# source_eagle.net
KiCad netlist of a schematic drawn in EAGLE
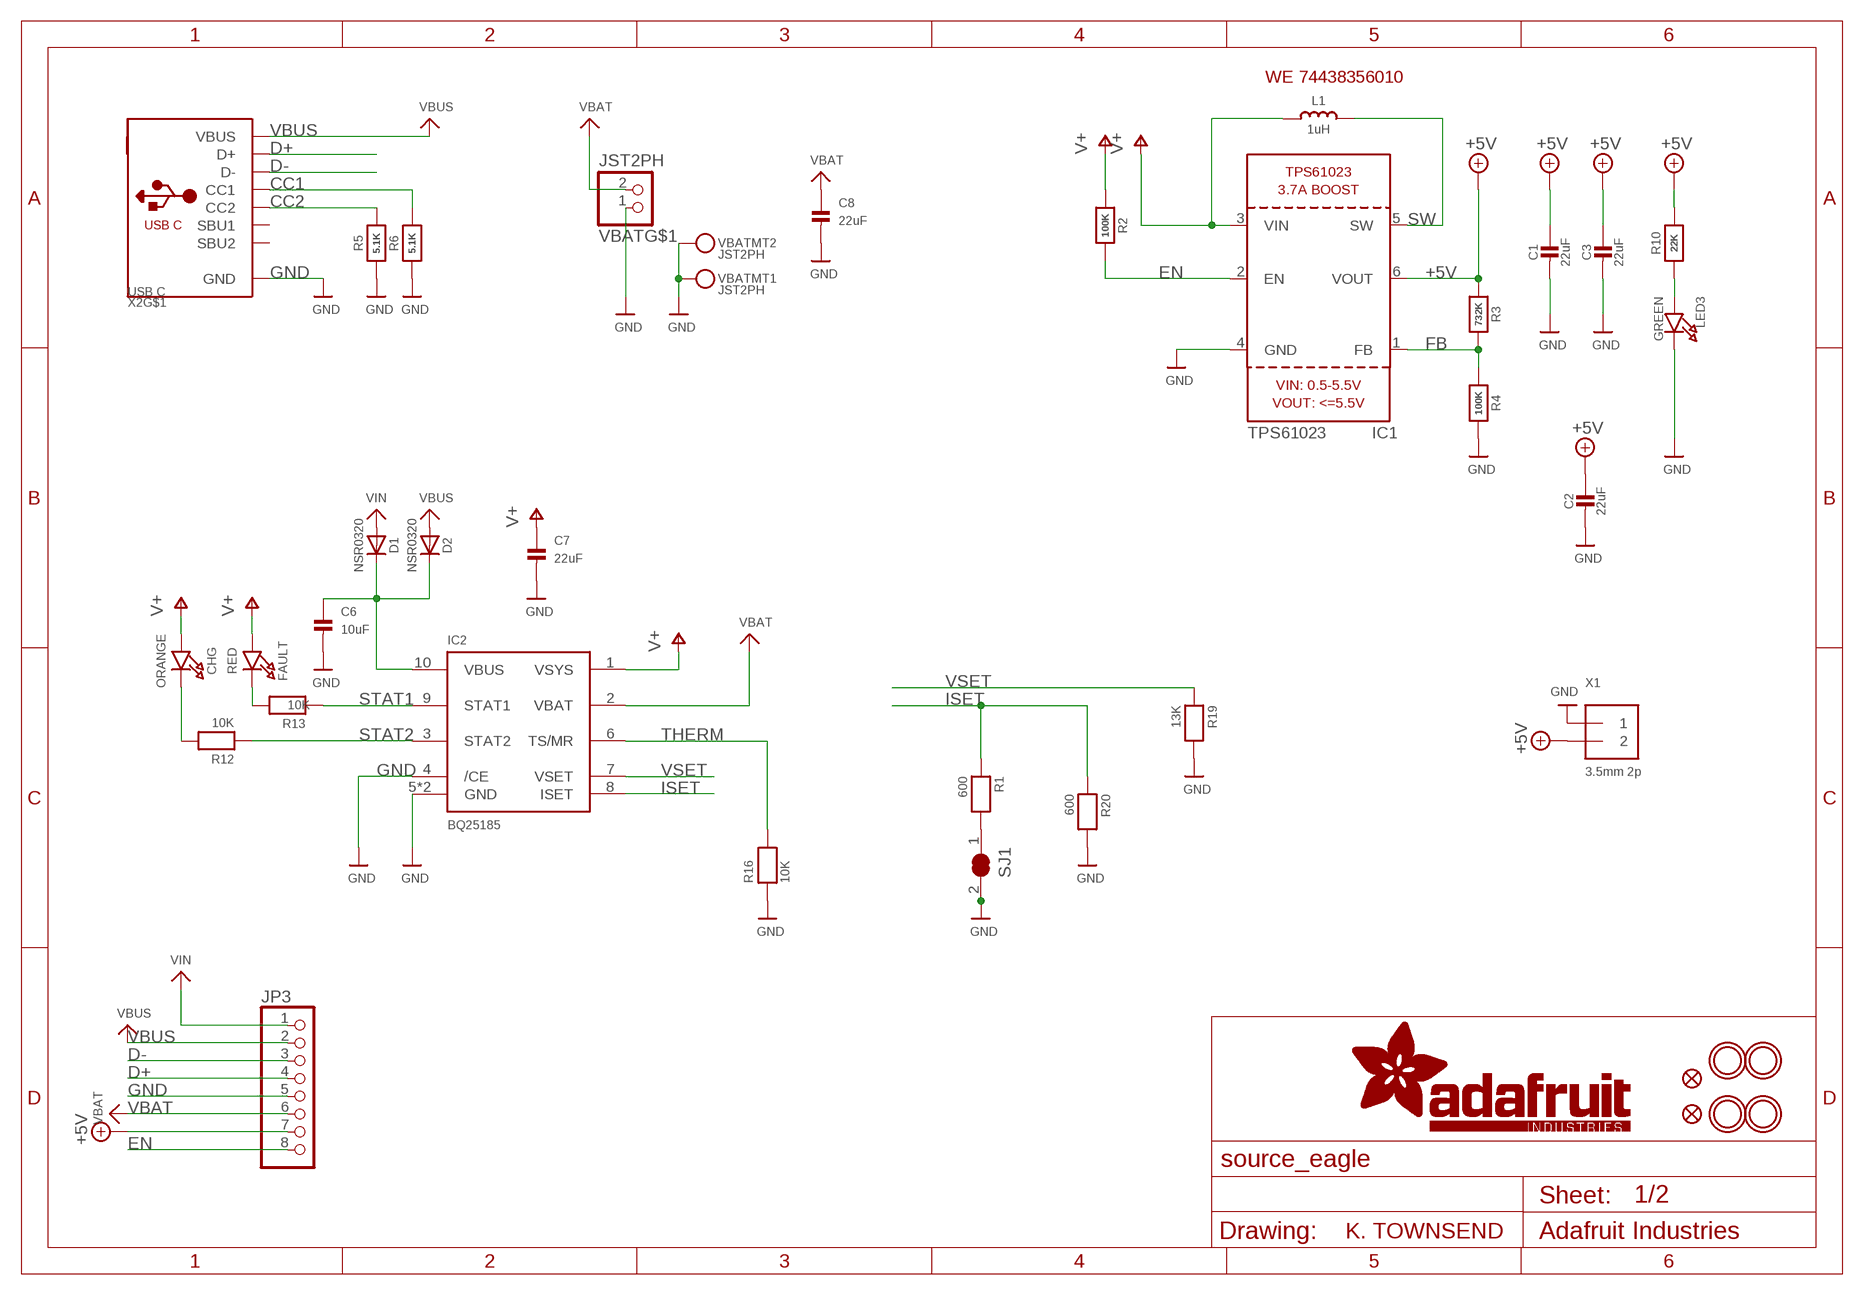
[diagram p0: schematic, sheet 1]
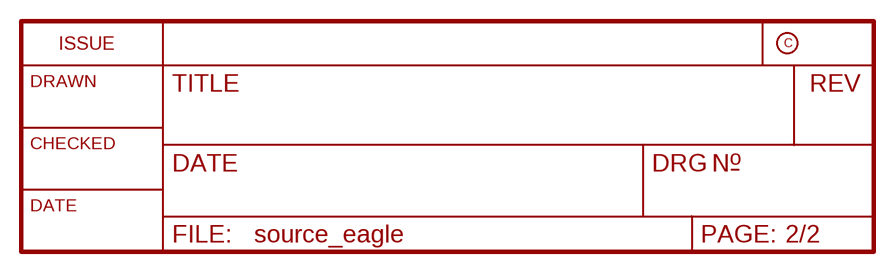
[diagram p1: schematic, sheet 2]

(export (version "E")
  (design (tool "Eeschema 10.0.6"))
  (components
    (comp (ref "C1")
      (value "22uF")
      (footprint "eagle-import:0805-NO")
      (libsource (lib "eagle-import") (part "CAP_CERAMIC0805-NOOUTLINE"))
    )
    (comp (ref "C2")
      (value "22uF")
      (footprint "eagle-import:0805-NO")
      (libsource (lib "eagle-import") (part "CAP_CERAMIC0805-NOOUTLINE"))
    )
    (comp (ref "C3")
      (value "22uF")
      (footprint "eagle-import:0805-NO")
      (libsource (lib "eagle-import") (part "CAP_CERAMIC0805-NOOUTLINE"))
    )
    (comp (ref "C6")
      (value "10uF")
      (footprint "eagle-import:0805-NO")
      (libsource (lib "eagle-import") (part "CAP_CERAMIC0805-NOOUTLINE"))
    )
    (comp (ref "C7")
      (value "22uF")
      (footprint "eagle-import:0805-NO")
      (libsource (lib "eagle-import") (part "CAP_CERAMIC0805-NOOUTLINE"))
    )
    (comp (ref "C8")
      (value "22uF")
      (footprint "eagle-import:0805-NO")
      (libsource (lib "eagle-import") (part "CAP_CERAMIC0805-NOOUTLINE"))
    )
    (comp (ref "CHG")
      (value "ORANGE")
      (footprint "eagle-import:CHIPLED_0603_NOOUTLINE")
      (libsource (lib "eagle-import") (part "LED0603_NOOUTLINE"))
    )
    (comp (ref "D1")
      (value "NSR0320")
      (footprint "eagle-import:SOD-323_MINI")
      (libsource (lib "eagle-import") (part "DIODE_SOD323MINI"))
    )
    (comp (ref "D2")
      (value "NSR0320")
      (footprint "eagle-import:SOD-323_MINI")
      (libsource (lib "eagle-import") (part "DIODE_SOD323MINI"))
    )
    (comp (ref "FAULT")
      (value "RED")
      (footprint "eagle-import:CHIPLED_0603_NOOUTLINE")
      (libsource (lib "eagle-import") (part "LED0603_NOOUTLINE"))
    )
    (comp (ref "FID1")
      (value "FIDUCIAL_0.5MM")
      (footprint "eagle-import:FIDUCIAL_0.5MM")
      (libsource (lib "eagle-import") (part "FIDUCIAL_0.5MM"))
    )
    (comp (ref "FID2")
      (value "FIDUCIAL_0.5MM")
      (footprint "eagle-import:FIDUCIAL_0.5MM")
      (libsource (lib "eagle-import") (part "FIDUCIAL_0.5MM"))
    )
    (comp (ref "IC1")
      (value "TPS61023")
      (footprint "eagle-import:SOT563")
      (libsource (lib "eagle-import") (part "TPS61023"))
    )
    (comp (ref "IC2")
      (value "BQ25185")
      (footprint "eagle-import:WSON10")
      (libsource (lib "eagle-import") (part "BQ25185"))
    )
    (comp (ref "JP3")
      (value "HEADER-1X870MIL")
      (footprint "eagle-import:1X08_ROUND_70")
      (libsource (lib "eagle-import") (part "HEADER-1X870MIL"))
    )
    (comp (ref "L1")
      (value "1uH")
      (footprint "eagle-import:INDUCTOR_5045_SMALLTABS")
      (libsource (lib "eagle-import") (part "INDUCTOR_5045_SMALLTABS"))
    )
    (comp (ref "LED3")
      (value "GREEN")
      (footprint "eagle-import:CHIPLED_0603_NOOUTLINE")
      (libsource (lib "eagle-import") (part "LED0603_NOOUTLINE"))
    )
    (comp (ref "R1")
      (value "600")
      (footprint "eagle-import:_0402NO")
      (libsource (lib "eagle-import") (part "RESISTOR_0402NO"))
    )
    (comp (ref "R2")
      (value "100K")
      (footprint "eagle-import:_0402NO")
      (libsource (lib "eagle-import") (part "RESISTOR_0402NO"))
    )
    (comp (ref "R3")
      (value "732K")
      (footprint "eagle-import:_0402NO")
      (libsource (lib "eagle-import") (part "RESISTOR_0402NO"))
    )
    (comp (ref "R4")
      (value "100K")
      (footprint "eagle-import:_0402NO")
      (libsource (lib "eagle-import") (part "RESISTOR_0402NO"))
    )
    (comp (ref "R5")
      (value "5.1K")
      (footprint "eagle-import:_0402NO")
      (libsource (lib "eagle-import") (part "RESISTOR_0402NO"))
    )
    (comp (ref "R6")
      (value "5.1K")
      (footprint "eagle-import:_0402NO")
      (libsource (lib "eagle-import") (part "RESISTOR_0402NO"))
    )
    (comp (ref "R10")
      (value "22K")
      (footprint "eagle-import:_0402NO")
      (libsource (lib "eagle-import") (part "RESISTOR_0402NO"))
    )
    (comp (ref "R12")
      (value "10K")
      (footprint "eagle-import:_0402NO")
      (libsource (lib "eagle-import") (part "RESISTOR_0402NO"))
    )
    (comp (ref "R13")
      (value "10K")
      (footprint "eagle-import:_0402NO")
      (libsource (lib "eagle-import") (part "RESISTOR_0402NO"))
    )
    (comp (ref "R16")
      (value "10K")
      (footprint "eagle-import:_0402NO")
      (libsource (lib "eagle-import") (part "RESISTOR_0402NO"))
    )
    (comp (ref "R19")
      (value "13K")
      (footprint "eagle-import:_0402NO")
      (libsource (lib "eagle-import") (part "RESISTOR_0402NO"))
    )
    (comp (ref "R20")
      (value "600")
      (footprint "eagle-import:_0402NO")
      (libsource (lib "eagle-import") (part "RESISTOR_0402NO"))
    )
    (comp (ref "SJ1")
      (value "SOLDERJUMPER_CLOSED")
      (footprint "eagle-import:SOLDERJUMPER_CLOSEDWIRE")
      (libsource (lib "eagle-import") (part "SOLDERJUMPER_CLOSED"))
    )
    (comp (ref "U$9")
      (value "MOUNTINGHOLE2.5")
      (footprint "eagle-import:MOUNTINGHOLE_2.5_PLATED")
      (libsource (lib "eagle-import") (part "MOUNTINGHOLE2.5"))
    )
    (comp (ref "U$10")
      (value "MOUNTINGHOLE2.5")
      (footprint "eagle-import:MOUNTINGHOLE_2.5_PLATED")
      (libsource (lib "eagle-import") (part "MOUNTINGHOLE2.5"))
    )
    (comp (ref "U$11")
      (value "MOUNTINGHOLE2.5")
      (footprint "eagle-import:MOUNTINGHOLE_2.5_PLATED")
      (libsource (lib "eagle-import") (part "MOUNTINGHOLE2.5"))
    )
    (comp (ref "U$12")
      (value "MOUNTINGHOLE2.5")
      (footprint "eagle-import:MOUNTINGHOLE_2.5_PLATED")
      (libsource (lib "eagle-import") (part "MOUNTINGHOLE2.5"))
    )
    (comp (ref "VBAT")
      (value "JST2PH")
      (footprint "eagle-import:JSTPH2_BATT")
      (libsource (lib "eagle-import") (part "CON_JST_PH_2PIN_MT_BATT"))
    )
    (comp (ref "X1")
      (value "3.5mm 2p")
      (footprint "eagle-import:TERMBLOCK_1X2-3.5MM")
      (libsource (lib "eagle-import") (part "TERMBLOCK_1X2_3.5MM"))
    )
    (comp (ref "X2")
      (value "USB C")
      (footprint "eagle-import:USB_C_CUSB31-CFM2AX-01-X")
      (libsource (lib "eagle-import") (part "USB_C"))
    )
  )
  (nets
    (net (code "1") (name "+5V") (class "Default")
      (node (ref "C1") (pin "1") (pinfunction "1_1") (pintype "passive"))
      (node (ref "C2") (pin "1") (pinfunction "1_1") (pintype "passive"))
      (node (ref "C3") (pin "1") (pinfunction "1_1") (pintype "passive"))
      (node (ref "IC1") (pin "6") (pinfunction "VOUT_6") (pintype "power_in"))
      (node (ref "JP3") (pin "7") (pinfunction "7_7") (pintype "passive"))
      (node (ref "R10") (pin "2") (pinfunction "2_2") (pintype "passive"))
      (node (ref "R3") (pin "1") (pinfunction "1_1") (pintype "passive"))
      (node (ref "X1") (pin "2") (pinfunction "2_2") (pintype "passive"))
    )
    (net (code "2") (name "CC1") (class "Default")
      (node (ref "R6") (pin "2") (pinfunction "2_2") (pintype "passive"))
      (node (ref "X2") (pin "A5") (pinfunction "CC1_A5") (pintype "bidirectional"))
    )
    (net (code "3") (name "CC2") (class "Default")
      (node (ref "R5") (pin "2") (pinfunction "2_2") (pintype "passive"))
      (node (ref "X2") (pin "B5") (pinfunction "CC2_B5") (pintype "bidirectional"))
    )
    (net (code "4") (name "D+") (class "Default")
      (node (ref "JP3") (pin "4") (pinfunction "4_4") (pintype "passive"))
      (node (ref "X2") (pin "A6") (pinfunction "D+_A6") (pintype "bidirectional"))
      (node (ref "X2") (pin "B6") (pinfunction "D+_B6") (pintype "bidirectional"))
    )
    (net (code "5") (name "D-") (class "Default")
      (node (ref "JP3") (pin "3") (pinfunction "3_3") (pintype "passive"))
      (node (ref "X2") (pin "A7") (pinfunction "D-_A7") (pintype "bidirectional"))
      (node (ref "X2") (pin "B7") (pinfunction "D-_B7") (pintype "bidirectional"))
    )
    (net (code "6") (name "EN") (class "Default")
      (node (ref "IC1") (pin "2") (pinfunction "EN_2") (pintype "input"))
      (node (ref "JP3") (pin "8") (pinfunction "8_8") (pintype "passive"))
      (node (ref "R2") (pin "2") (pinfunction "2_2") (pintype "passive"))
    )
    (net (code "7") (name "FB") (class "Default")
      (node (ref "IC1") (pin "1") (pinfunction "FB_1") (pintype "input"))
      (node (ref "R3") (pin "2") (pinfunction "2_2") (pintype "passive"))
      (node (ref "R4") (pin "1") (pinfunction "1_1") (pintype "passive"))
    )
    (net (code "8") (name "GND") (class "Default")
      (node (ref "C1") (pin "2") (pinfunction "2_2") (pintype "passive"))
      (node (ref "C2") (pin "2") (pinfunction "2_2") (pintype "passive"))
      (node (ref "C3") (pin "2") (pinfunction "2_2") (pintype "passive"))
      (node (ref "C6") (pin "2") (pinfunction "2_2") (pintype "passive"))
      (node (ref "C7") (pin "2") (pinfunction "2_2") (pintype "passive"))
      (node (ref "C8") (pin "2") (pinfunction "2_2") (pintype "passive"))
      (node (ref "IC1") (pin "4") (pinfunction "GND_4") (pintype "power_in"))
      (node (ref "IC2") (pin "4") (pinfunction "/CE_4") (pintype "input"))
      (node (ref "IC2") (pin "5") (pinfunction "GND_5") (pintype "bidirectional"))
      (node (ref "IC2") (pin "PAD") (pinfunction "GND_PAD") (pintype "bidirectional"))
      (node (ref "JP3") (pin "5") (pinfunction "5_5") (pintype "passive"))
      (node (ref "LED3") (pin "C") (pinfunction "C_C") (pintype "passive"))
      (node (ref "R16") (pin "1") (pinfunction "1_1") (pintype "passive"))
      (node (ref "R19") (pin "2") (pinfunction "2_2") (pintype "passive"))
      (node (ref "R20") (pin "2") (pinfunction "2_2") (pintype "passive"))
      (node (ref "R4") (pin "2") (pinfunction "2_2") (pintype "passive"))
      (node (ref "R5") (pin "1") (pinfunction "1_1") (pintype "passive"))
      (node (ref "R6") (pin "1") (pinfunction "1_1") (pintype "passive"))
      (node (ref "SJ1") (pin "2") (pinfunction "2_2") (pintype "passive"))
      (node (ref "VBAT") (pin "1") (pinfunction "1_1") (pintype "passive"))
      (node (ref "VBAT") (pin "NC1") (pinfunction "P$1_NC1") (pintype "bidirectional"))
      (node (ref "VBAT") (pin "NC2") (pinfunction "P$1_NC2") (pintype "bidirectional"))
      (node (ref "X1") (pin "1") (pinfunction "1_1") (pintype "passive"))
      (node (ref "X2") (pin "A1B12") (pinfunction "GND_A1B12") (pintype "power_in"))
      (node (ref "X2") (pin "B1A12") (pinfunction "GND_B1A12") (pintype "power_in"))
    )
    (net (code "9") (name "ISET") (class "Default")
      (node (ref "IC2") (pin "8") (pinfunction "ISET_8") (pintype "bidirectional"))
      (node (ref "R1") (pin "1") (pinfunction "1_1") (pintype "passive"))
      (node (ref "R20") (pin "1") (pinfunction "1_1") (pintype "passive"))
    )
    (net (code "10") (name "Net-(CHG-PadC)") (class "Default")
      (node (ref "CHG") (pin "C") (pinfunction "C_C") (pintype "passive"))
      (node (ref "R12") (pin "2") (pinfunction "2_2") (pintype "passive"))
    )
    (net (code "11") (name "Net-(FAULT-PadC)") (class "Default")
      (node (ref "FAULT") (pin "C") (pinfunction "C_C") (pintype "passive"))
      (node (ref "R13") (pin "2") (pinfunction "2_2") (pintype "passive"))
    )
    (net (code "12") (name "Net-(IC2-VBUS)") (class "Default")
      (node (ref "C6") (pin "1") (pinfunction "1_1") (pintype "passive"))
      (node (ref "D1") (pin "C") (pinfunction "C_C") (pintype "passive"))
      (node (ref "D2") (pin "C") (pinfunction "C_C") (pintype "passive"))
      (node (ref "IC2") (pin "10") (pinfunction "VBUS_10") (pintype "power_in"))
    )
    (net (code "13") (name "Net-(LED3-PadA)") (class "Default")
      (node (ref "LED3") (pin "A") (pinfunction "A_A") (pintype "passive"))
      (node (ref "R10") (pin "1") (pinfunction "1_1") (pintype "passive"))
    )
    (net (code "14") (name "Net-(R1-Pad2)") (class "Default")
      (node (ref "R1") (pin "2") (pinfunction "2_2") (pintype "passive"))
      (node (ref "SJ1") (pin "1") (pinfunction "1_1") (pintype "passive"))
    )
    (net (code "15") (name "STAT1") (class "Default")
      (node (ref "IC2") (pin "9") (pinfunction "STAT1_9") (pintype "bidirectional"))
      (node (ref "R13") (pin "1") (pinfunction "1_1") (pintype "passive"))
    )
    (net (code "16") (name "STAT2") (class "Default")
      (node (ref "IC2") (pin "3") (pinfunction "STAT2_3") (pintype "bidirectional"))
      (node (ref "R12") (pin "1") (pinfunction "1_1") (pintype "passive"))
    )
    (net (code "17") (name "SW") (class "Default")
      (node (ref "IC1") (pin "5") (pinfunction "SW_5") (pintype "input"))
      (node (ref "L1") (pin "2") (pinfunction "2_2") (pintype "passive"))
    )
    (net (code "18") (name "THERM") (class "Default")
      (node (ref "IC2") (pin "6") (pinfunction "TS/MR_6") (pintype "bidirectional"))
      (node (ref "R16") (pin "2") (pinfunction "2_2") (pintype "passive"))
    )
    (net (code "19") (name "V+") (class "Default")
      (node (ref "C7") (pin "1") (pinfunction "1_1") (pintype "passive"))
      (node (ref "CHG") (pin "A") (pinfunction "A_A") (pintype "passive"))
      (node (ref "FAULT") (pin "A") (pinfunction "A_A") (pintype "passive"))
      (node (ref "IC1") (pin "3") (pinfunction "VIN_3") (pintype "power_in"))
      (node (ref "IC2") (pin "1") (pinfunction "VSYS_1") (pintype "power_in"))
      (node (ref "L1") (pin "1") (pinfunction "1_1") (pintype "passive"))
      (node (ref "R2") (pin "1") (pinfunction "1_1") (pintype "passive"))
    )
    (net (code "20") (name "VBAT") (class "Default")
      (node (ref "C8") (pin "1") (pinfunction "1_1") (pintype "passive"))
      (node (ref "IC2") (pin "2") (pinfunction "VBAT_2") (pintype "input"))
      (node (ref "JP3") (pin "6") (pinfunction "6_6") (pintype "passive"))
      (node (ref "VBAT") (pin "2") (pinfunction "2_2") (pintype "passive"))
    )
    (net (code "21") (name "VBUS") (class "Default")
      (node (ref "D2") (pin "A") (pinfunction "A_A") (pintype "passive"))
      (node (ref "JP3") (pin "2") (pinfunction "2_2") (pintype "passive"))
      (node (ref "X2") (pin "A4B9") (pinfunction "VBUS_A4B9") (pintype "power_in"))
      (node (ref "X2") (pin "B4A9") (pinfunction "VBUS_B4A9") (pintype "power_in"))
    )
    (net (code "22") (name "VIN") (class "Default")
      (node (ref "D1") (pin "A") (pinfunction "A_A") (pintype "passive"))
      (node (ref "JP3") (pin "1") (pinfunction "1_1") (pintype "passive"))
    )
    (net (code "23") (name "VSET") (class "Default")
      (node (ref "IC2") (pin "7") (pinfunction "VSET_7") (pintype "bidirectional"))
      (node (ref "R19") (pin "1") (pinfunction "1_1") (pintype "passive"))
    )
    (net (code "24") (name "unconnected-(X2A-SBU1-PadA8)") (class "Default")
      (node (ref "X2") (pin "A8") (pinfunction "SBU1_A8") (pintype "bidirectional"))
    )
    (net (code "25") (name "unconnected-(X2A-SBU2-PadB8)") (class "Default")
      (node (ref "X2") (pin "B8") (pinfunction "SBU2_B8") (pintype "bidirectional"))
    )
  )
)
